# Main.net
KiCad netlist of a schematic drawn in Altium Designer
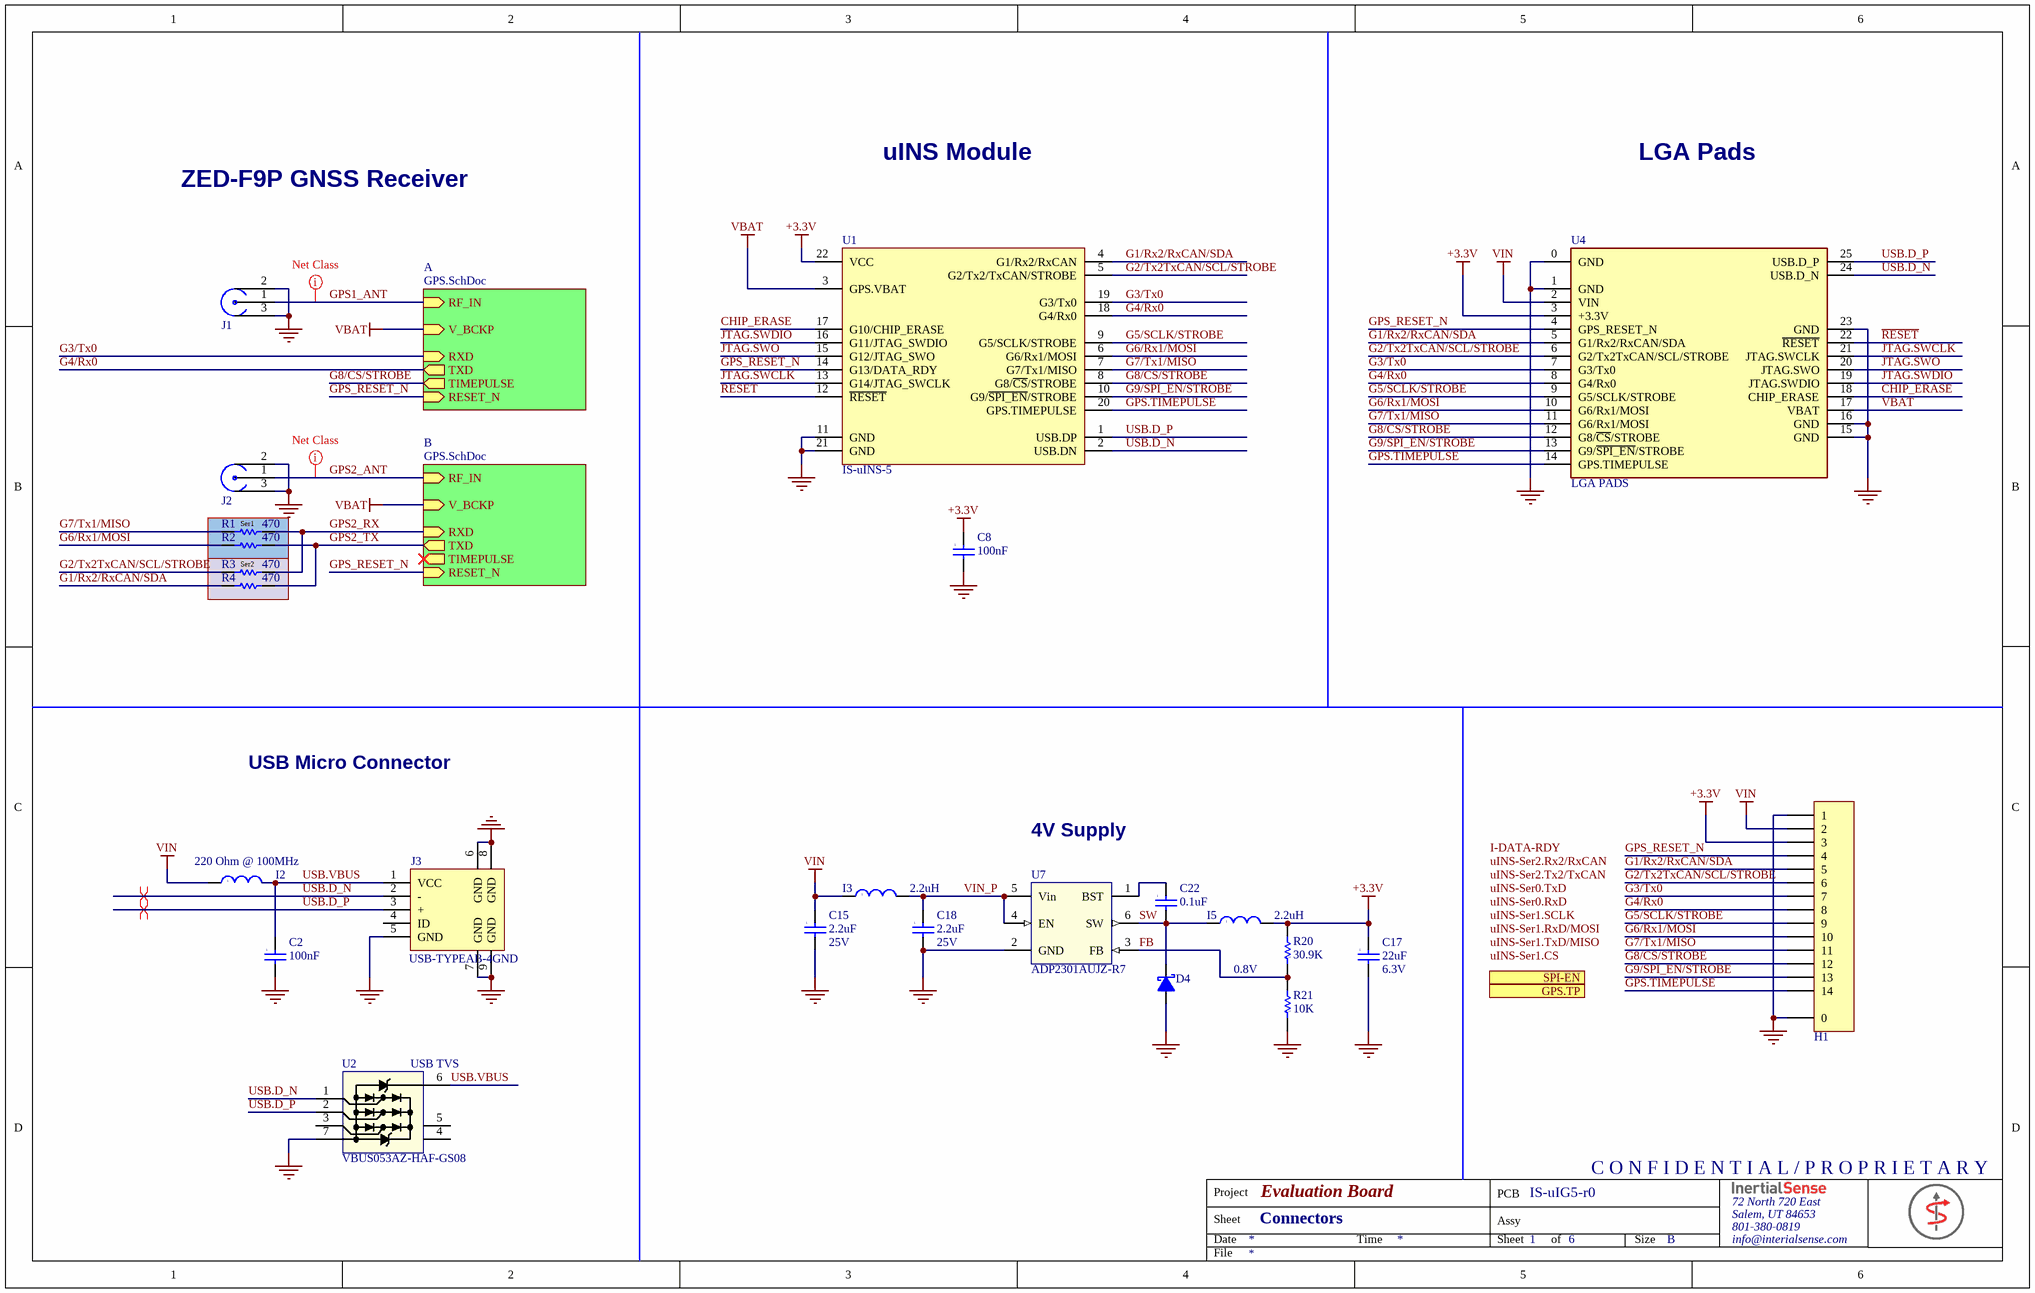
[diagram p0: Main.SchDoc]

(export (version "E")
  (design (tool "Eeschema 10.0.6"))
  (components
    (comp (ref "C2")
      (value "100nF")
      (footprint "0402")
      (description "CAP CER .10UF 50V X7R 10% 0402")
      (fields
        (field (name "MANUFACTURER") "TDK Corporation")
        (field (name "MANUFACTURER PART NUMBER") "C1005X7R1H104K")
        (field (name "PUBLISHER") "Altium Limited")
      )
      (libsource (lib "General") (part "Cap"))
    )
    (comp (ref "C8")
      (value "100nF")
      (footprint "0402")
      (description "CAP CER .10UF 50V X7R 10% 0402")
      (fields
        (field (name "MANUFACTURER") "TDK Corporation")
        (field (name "MANUFACTURER PART NUMBER") "C1005X7R1H104K")
        (field (name "PUBLISHER") "Altium Limited")
      )
      (libsource (lib "General") (part "Cap"))
    )
    (comp (ref "C15")
      (value "2.2uF")
      (footprint "0603")
      (description "CAP CER 2.2UF 25V X6S 0603")
      (fields
        (field (name "MANUFACTURER") "Murata")
        (field (name "MANUFACTURER PART NUMBER") "GRT188C81E225KE13D")
        (field (name "VOLTAGE RATING") "25V")
        (field (name "PUBLISHER") "Altium Limited")
      )
      (libsource (lib "") (part "Cap_1"))
    )
    (comp (ref "C17")
      (value "22uF")
      (footprint "0603")
      (description "CAP CER 22UF 6.3V X6S 0603")
      (fields
        (field (name "MANUFACTURER") "Murata")
        (field (name "MANUFACTURER PART NUMBER") "GRM188C80J226ME15D")
        (field (name "VOLTAGE RATING") "6.3V")
        (field (name "PUBLISHER") "Altium Limited")
      )
      (libsource (lib "") (part "Cap_1"))
    )
    (comp (ref "C18")
      (value "2.2uF")
      (footprint "0603")
      (description "CAP CER 2.2UF 25V X6S 0603")
      (fields
        (field (name "MANUFACTURER") "Murata")
        (field (name "MANUFACTURER PART NUMBER") "GRT188C81E225KE13D")
        (field (name "VOLTAGE RATING") "25V")
        (field (name "PUBLISHER") "Altium Limited")
      )
      (libsource (lib "") (part "Cap_1"))
    )
    (comp (ref "C22")
      (value "0.1uF")
      (footprint "0402")
      (description "CAP CER 0.1UF 50V X7R 0402")
      (fields
        (field (name "MANUFACTURER") "TDK")
        (field (name "MANUFACTURER PART NUMBER") "CGA2B3X7R1H104K050BB")
        (field (name "PUBLISHER") "Altium Limited")
      )
      (libsource (lib "") (part "Cap_1"))
    )
    (comp (ref "D4")
      (value "Diode - Schottky")
      (footprint "D0603B")
      (description "DIODE SCHOTTKY 30V 2A 0603")
      (fields
        (field (name "MANUFACTURER") "Vishay")
        (field (name "MANUFACTURER PART NUMBER") "VSKY20301608-G4-08")
      )
      (libsource (lib "General") (part "Diode - Schottky"))
    )
    (comp (ref "H1")
      (value "Hdr - 14pin - mount")
      (footprint "SM14B-GHS-TB(LF)(SN)")
      (description "Conn Shrouded Header HDR 14 POS 1.25mm Solder ST Top Entry SMD T/R")
      (fields
        (field (name "MANUFACTURER") "JST")
        (field (name "MANUFACTURER PART NUMBER") "SM14B-GHS-TB(LF)(SN)")
      )
      (libsource (lib "Connectors") (part "Hdr - 14pin - mount"))
    )
    (comp (ref "I2")
      (value "220 Ohm @ 100MHz")
      (footprint "I0603")
      (description "FERRITE CHIP 220 OHM 2500MA 0603")
      (fields
        (field (name "MANUFACTURER") "Murata Electronics North America")
        (field (name "MANUFACTURER PART NUMBER") "BLM18SG221TN1D")
      )
      (libsource (lib "") (part "Inductor_1"))
    )
    (comp (ref "I3")
      (value "2.2uH")
      (footprint "0806")
      (description "FIXED IND 2.2UH 1.2A 110 MOHM")
      (fields
        (field (name "MANUFACTURER") "TDK")
        (field (name "MANUFACTURER PART NUMBER") "MLP2016H2R2MT0S1")
      )
      (libsource (lib "General") (part "Inductor"))
    )
    (comp (ref "I5")
      (value "2.2uH")
      (footprint "0806")
      (description "FIXED IND 2.2UH 1.2A 110 MOHM")
      (fields
        (field (name "MANUFACTURER") "TDK")
        (field (name "MANUFACTURER PART NUMBER") "MLP2016H2R2MT0S1")
      )
      (libsource (lib "General") (part "Inductor"))
    )
    (comp (ref "J1")
      (value "RF - GND x 2")
      (footprint "RF UMC SMD")
      (description "CONN UMC RCPT STR 50 OHM SMD")
      (fields
        (field (name "MANUFACTURER") "Emerson Network Power Connectivity Johnson")
        (field (name "MANUFACTURER PART NUMBER") "128-0711-201")
      )
      (libsource (lib "Connectors") (part "RF - GND x 2"))
    )
    (comp (ref "J2")
      (value "RF - GND x 2")
      (footprint "RF UMC SMD")
      (description "CONN UMC RCPT STR 50 OHM SMD")
      (fields
        (field (name "MANUFACTURER") "Emerson Network Power Connectivity Johnson")
        (field (name "MANUFACTURER PART NUMBER") "128-0711-201")
      )
      (libsource (lib "Connectors") (part "RF - GND x 2"))
    )
    (comp (ref "J3")
      (value "USB-TYPEAB-4GND")
      (footprint "USB Micro AB R/A THR")
      (description "CONN USB AB 4POS")
      (fields
        (field (name "MANUFACTURER") "Amphenol FCI")
        (field (name "MANUFACTURER PART NUMBER") "10118194-0001LF")
      )
      (libsource (lib "Connectors") (part "USB-TYPEAB-4GND"))
    )
    (comp (ref "R1")
      (value "470")
      (footprint "R0402")
      (description "RES 470 OHM 1/16W 1% 0402 SMD")
      (fields
        (field (name "MANUFACTURER") "Vishay Dale")
        (field (name "MANUFACTURER PART NUMBER") "CRCW0402470RFKED")
      )
      (libsource (lib "") (part "Res_1"))
    )
    (comp (ref "R2")
      (value "470")
      (footprint "R0402")
      (description "RES 470 OHM 1/16W 1% 0402 SMD")
      (fields
        (field (name "MANUFACTURER") "Vishay Dale")
        (field (name "MANUFACTURER PART NUMBER") "CRCW0402470RFKED")
      )
      (libsource (lib "") (part "Res_1"))
    )
    (comp (ref "R3")
      (value "470")
      (footprint "R0402")
      (description "RES 470 OHM 1/16W 1% 0402 SMD")
      (fields
        (field (name "MANUFACTURER") "Vishay Dale")
        (field (name "MANUFACTURER PART NUMBER") "CRCW0402470RFKED")
      )
      (libsource (lib "") (part "Res_1"))
    )
    (comp (ref "R4")
      (value "470")
      (footprint "R0402")
      (description "RES 470 OHM 1/16W 1% 0402 SMD")
      (fields
        (field (name "MANUFACTURER") "Vishay Dale")
        (field (name "MANUFACTURER PART NUMBER") "CRCW0402470RFKED")
      )
      (libsource (lib "") (part "Res_1"))
    )
    (comp (ref "R20")
      (value "30.9K")
      (footprint "R0402")
      (description "RES TF 30.9K OHM 1% 1/16W 0402")
      (fields
        (field (name "MANUFACTURER") "Stackpole Electronics Inc")
        (field (name "MANUFACTURER PART NUMBER") "RMCF0402FT30K9")
      )
      (libsource (lib "General") (part "Res"))
    )
    (comp (ref "R21")
      (value "10K")
      (footprint "R0402")
      (description "RES 10.0K OHM 1/16W 1% 0402 SMD")
      (fields
        (field (name "MANUFACTURER") "Yageo")
        (field (name "MANUFACTURER PART NUMBER") "RC0402FR-0710KL")
      )
      (libsource (lib "General") (part "Res"))
    )
    (comp (ref "U1")
      (value "uINS")
      (footprint "IS-uINS-5.0")
      (description "Inertial Sense uINS")
      (fields
        (field (name "MANUFACTURER") "Inertial Sense")
        (field (name "MANUFACTURER PART NUMBER") "IS-uINS-5")
      )
      (libsource (lib "IS-uINS-5") (part "IS-uINS-5.0"))
    )
    (comp (ref "U2")
      (value "VBUS053")
      (footprint "QFN50P160X160X60-6N")
      (description "ESD SUPPRESS 5.5V 36W 3-Line USB")
      (fields
        (field (name "MANUFACTURER") "Vishay Semiconductors")
        (field (name "MANUFACTURER PART NUMBER") "VBUS053AZ-HAF-GS08")
      )
      (libsource (lib "ICs") (part "VBUS053"))
    )
    (comp (ref "U4")
      (value "LGA PADS")
      (footprint "uIG5p1_LGA")
      (description "Inertial Sense uIG5 GNSS INS Module")
      (libsource (lib "Sensors") (part "uIG5p0_LGA"))
    )
    (comp (ref "U7")
      (value "ADP2301")
      (footprint "MO-178-AB")
      (description "IC BUCK ADJ 1.2A 6TSOT")
      (fields
        (field (name "MANUFACTURER") "Analog Devices Inc")
        (field (name "MANUFACTURER PART NUMBER") "ADP2301AUJZ-R7")
      )
      (libsource (lib "ICs") (part "ADP2301"))
    )
  )
  (nets
    (net (code "1") (name "+3.3V") (class "Default")
      (node (ref "C17") (pin "1") (pinfunction "1_1") (pintype "passive"))
      (node (ref "C8") (pin "1") (pinfunction "1_1") (pintype "passive"))
      (node (ref "H1") (pin "3") (pinfunction "3_3") (pintype "passive"))
      (node (ref "I5") (pin "2") (pinfunction "2_2") (pintype "passive"))
      (node (ref "R20") (pin "2") (pinfunction "2_2") (pintype "passive"))
      (node (ref "U1") (pin "22") (pinfunction "VCC_22") (pintype "power_in"))
      (node (ref "U4") (pin "3") (pinfunction "+3.3V_3") (pintype "passive"))
    )
    (net (code "2") (name "/CHIP_ERASE") (class "Default")
      (node (ref "U1") (pin "17") (pinfunction "G10/CHIP_ERASE_17") (pintype "passive"))
      (node (ref "U4") (pin "18") (pinfunction "CHIP_ERASE_18") (pintype "passive"))
    )
    (net (code "3") (name "/FB") (class "Default")
      (node (ref "R20") (pin "1") (pinfunction "1_1") (pintype "passive"))
      (node (ref "R21") (pin "2") (pinfunction "2_2") (pintype "passive"))
      (node (ref "U7") (pin "3") (pinfunction "FB_3") (pintype "input"))
    )
    (net (code "4") (name "/G1{slash}Rx2{slash}RxCAN{slash}SDA") (class "Default")
      (node (ref "H1") (pin "5") (pinfunction "5_5") (pintype "passive"))
      (node (ref "R4") (pin "1") (pinfunction "1_1") (pintype "passive"))
      (node (ref "U1") (pin "4") (pinfunction "G1/Rx2/RxCAN_4") (pintype "passive"))
      (node (ref "U4") (pin "5") (pinfunction "G1/Rx2/RxCAN/SDA_5") (pintype "passive"))
    )
    (net (code "5") (name "/G2{slash}Tx2TxCAN{slash}SCL{slash}STROBE") (class "Default")
      (node (ref "H1") (pin "6") (pinfunction "6_6") (pintype "passive"))
      (node (ref "R3") (pin "1") (pinfunction "1_1") (pintype "passive"))
      (node (ref "U1") (pin "5") (pinfunction "G2/Tx2/TxCAN/STROBE_5") (pintype "passive"))
      (node (ref "U4") (pin "6") (pinfunction "G2/Tx2TxCAN/SCL/STROBE_6") (pintype "passive"))
    )
    (net (code "6") (name "/G3{slash}Tx0") (class "Default")
      (node (ref "H1") (pin "7") (pinfunction "7_7") (pintype "passive"))
      (node (ref "U1") (pin "19") (pinfunction "G3/Tx0_19") (pintype "passive"))
      (node (ref "U4") (pin "7") (pinfunction "G3/Tx0_7") (pintype "passive"))
    )
    (net (code "7") (name "/G4{slash}Rx0") (class "Default")
      (node (ref "H1") (pin "8") (pinfunction "8_8") (pintype "passive"))
      (node (ref "U1") (pin "18") (pinfunction "G4/Rx0_18") (pintype "passive"))
      (node (ref "U4") (pin "8") (pinfunction "G4/Rx0_8") (pintype "passive"))
    )
    (net (code "8") (name "/G5{slash}SCLK{slash}STROBE") (class "Default")
      (node (ref "H1") (pin "9") (pinfunction "9_9") (pintype "passive"))
      (node (ref "U1") (pin "9") (pinfunction "G5/SCLK/STROBE_9") (pintype "passive"))
      (node (ref "U4") (pin "9") (pinfunction "G5/SCLK/STROBE_9") (pintype "passive"))
    )
    (net (code "9") (name "/G6{slash}Rx1{slash}MOSI") (class "Default")
      (node (ref "H1") (pin "10") (pinfunction "10_10") (pintype "passive"))
      (node (ref "R2") (pin "1") (pinfunction "1_1") (pintype "passive"))
      (node (ref "U1") (pin "6") (pinfunction "G6/Rx1/MOSI_6") (pintype "passive"))
      (node (ref "U4") (pin "10") (pinfunction "G6/Rx1/MOSI_10") (pintype "passive"))
    )
    (net (code "10") (name "/G7{slash}Tx1{slash}MISO") (class "Default")
      (node (ref "H1") (pin "11") (pinfunction "11_11") (pintype "passive"))
      (node (ref "R1") (pin "1") (pinfunction "1_1") (pintype "passive"))
      (node (ref "U1") (pin "7") (pinfunction "G7/Tx1/MISO_7") (pintype "passive"))
      (node (ref "U4") (pin "11") (pinfunction "G6/Rx1/MOSI_11") (pintype "passive"))
    )
    (net (code "11") (name "/G8{slash}~{CS}{slash}STROBE") (class "Default")
      (node (ref "H1") (pin "12") (pinfunction "12_12") (pintype "passive"))
      (node (ref "U1") (pin "8") (pinfunction "G8/~{CS}/STROBE_8") (pintype "passive"))
      (node (ref "U4") (pin "12") (pinfunction "G8/~{CS}/STROBE_12") (pintype "passive"))
    )
    (net (code "12") (name "/G9{slash}~{SPI_EN}{slash}STROBE") (class "Default")
      (node (ref "H1") (pin "13") (pinfunction "13_13") (pintype "passive"))
      (node (ref "U1") (pin "10") (pinfunction "G9/~{SPI_EN}/STROBE_10") (pintype "passive"))
      (node (ref "U4") (pin "13") (pinfunction "G9/~{SPI_EN}/STROBE_13") (pintype "passive"))
    )
    (net (code "13") (name "/GPS.TIMEPULSE") (class "Default")
      (node (ref "H1") (pin "14") (pinfunction "14_14") (pintype "passive"))
      (node (ref "U1") (pin "20") (pinfunction "GPS.TIMEPULSE_20") (pintype "passive"))
      (node (ref "U4") (pin "14") (pinfunction "GPS.TIMEPULSE_14") (pintype "passive"))
    )
    (net (code "15") (name "/GPS1_ANT") (class "Default")
      (node (ref "J1") (pin "1") (pinfunction "1_1") (pintype "passive"))
    )
    (net (code "16") (name "/GPS2_ANT") (class "Default")
      (node (ref "J2") (pin "1") (pinfunction "1_1") (pintype "passive"))
    )
    (net (code "17") (name "/GPS2_RX") (class "Default")
      (node (ref "R1") (pin "2") (pinfunction "2_2") (pintype "passive"))
      (node (ref "R3") (pin "2") (pinfunction "2_2") (pintype "passive"))
    )
    (net (code "18") (name "/GPS2_TX") (class "Default")
      (node (ref "R2") (pin "2") (pinfunction "2_2") (pintype "passive"))
      (node (ref "R4") (pin "2") (pinfunction "2_2") (pintype "passive"))
    )
    (net (code "19") (name "/GPS_RESET_N") (class "Default")
      (node (ref "H1") (pin "4") (pinfunction "4_4") (pintype "passive"))
      (node (ref "U1") (pin "14") (pinfunction "G13/DATA_RDY_14") (pintype "passive"))
      (node (ref "U4") (pin "4") (pinfunction "GPS_RESET_N_4") (pintype "passive"))
    )
    (net (code "21") (name "/JTAG.SWCLK") (class "Default")
      (node (ref "U1") (pin "13") (pinfunction "G14/JTAG_SWCLK_13") (pintype "passive"))
      (node (ref "U4") (pin "21") (pinfunction "JTAG.SWCLK_21") (pintype "passive"))
    )
    (net (code "22") (name "/JTAG.SWDIO") (class "Default")
      (node (ref "U1") (pin "16") (pinfunction "G11/JTAG_SWDIO_16") (pintype "passive"))
      (node (ref "U4") (pin "19") (pinfunction "JTAG.SWDIO_19") (pintype "passive"))
    )
    (net (code "23") (name "/JTAG.SWO") (class "Default")
      (node (ref "U1") (pin "15") (pinfunction "G12/JTAG_SWO_15") (pintype "passive"))
      (node (ref "U4") (pin "20") (pinfunction "JTAG.SWO_20") (pintype "passive"))
    )
    (net (code "24") (name "/RESET") (class "Default")
      (node (ref "U1") (pin "12") (pinfunction "~{RESET}_12") (pintype "passive"))
      (node (ref "U4") (pin "22") (pinfunction "~{RESET}_22") (pintype "passive"))
    )
    (net (code "26") (name "/SW") (class "Default")
      (node (ref "C22") (pin "2") (pinfunction "2_2") (pintype "passive"))
      (node (ref "D4") (pin "C") (pinfunction "C_C") (pintype "passive"))
      (node (ref "I5") (pin "1") (pinfunction "1_1") (pintype "passive"))
      (node (ref "U7") (pin "6") (pinfunction "SW_6") (pintype "output"))
    )
    (net (code "28") (name "/USB.D_N") (class "Default")
      (node (ref "J3") (pin "2") (pinfunction "-_2") (pintype "passive"))
      (node (ref "U1") (pin "2") (pinfunction "USB.DN_2") (pintype "passive"))
      (node (ref "U2") (pin "1") (pintype "passive"))
      (node (ref "U4") (pin "24") (pinfunction "USB.D_N_24") (pintype "passive"))
    )
    (net (code "29") (name "/USB.D_P") (class "Default")
      (node (ref "J3") (pin "3") (pinfunction "+_3") (pintype "passive"))
      (node (ref "U1") (pin "1") (pinfunction "USB.DP_1") (pintype "passive"))
      (node (ref "U2") (pin "2") (pintype "passive"))
      (node (ref "U4") (pin "25") (pinfunction "USB.D_P_25") (pintype "passive"))
    )
    (net (code "30") (name "/USB.VBUS") (class "Default")
      (node (ref "C2") (pin "1") (pinfunction "1_1") (pintype "passive"))
      (node (ref "I2") (pin "2") (pinfunction "2_2") (pintype "passive"))
      (node (ref "J3") (pin "1") (pinfunction "VCC_1") (pintype "passive"))
      (node (ref "U2") (pin "6") (pintype "passive"))
    )
    (net (code "31") (name "/VIN_P") (class "Default")
      (node (ref "C18") (pin "1") (pinfunction "1_1") (pintype "passive"))
      (node (ref "I3") (pin "2") (pinfunction "2_2") (pintype "passive"))
      (node (ref "U7") (pin "4") (pinfunction "EN_4") (pintype "input"))
      (node (ref "U7") (pin "5") (pinfunction "Vin_5") (pintype "power_in"))
    )
    (net (code "40") (name "GND") (class "Default")
      (node (ref "C15") (pin "2") (pinfunction "2_2") (pintype "passive"))
      (node (ref "C17") (pin "2") (pinfunction "2_2") (pintype "passive"))
      (node (ref "C18") (pin "2") (pinfunction "2_2") (pintype "passive"))
      (node (ref "C2") (pin "2") (pinfunction "2_2") (pintype "passive"))
      (node (ref "C8") (pin "2") (pinfunction "2_2") (pintype "passive"))
      (node (ref "D4") (pin "A") (pinfunction "A_A") (pintype "passive"))
      (node (ref "H1") (pin "0") (pinfunction "0_0") (pintype "passive"))
      (node (ref "H1") (pin "1") (pinfunction "1_1") (pintype "passive"))
      (node (ref "J1") (pin "2") (pinfunction "2_2") (pintype "passive"))
      (node (ref "J1") (pin "3") (pinfunction "3_3") (pintype "passive"))
      (node (ref "J2") (pin "2") (pinfunction "2_2") (pintype "passive"))
      (node (ref "J2") (pin "3") (pinfunction "3_3") (pintype "passive"))
      (node (ref "J3") (pin "5") (pinfunction "GND_5") (pintype "passive"))
      (node (ref "J3") (pin "6") (pinfunction "GND_6") (pintype "passive"))
      (node (ref "J3") (pin "7") (pinfunction "GND_7") (pintype "passive"))
      (node (ref "J3") (pin "8") (pinfunction "GND_8") (pintype "passive"))
      (node (ref "J3") (pin "9") (pinfunction "GND_9") (pintype "passive"))
      (node (ref "R21") (pin "1") (pinfunction "1_1") (pintype "passive"))
      (node (ref "U1") (pin "11") (pinfunction "GND_11") (pintype "power_in"))
      (node (ref "U1") (pin "21") (pinfunction "GND_21") (pintype "power_in"))
      (node (ref "U2") (pin "7") (pintype "passive"))
      (node (ref "U4") (pin "0") (pinfunction "GND_0") (pintype "passive"))
      (node (ref "U4") (pin "1") (pinfunction "GND_1") (pintype "passive"))
      (node (ref "U4") (pin "15") (pinfunction "GND_15") (pintype "passive"))
      (node (ref "U4") (pin "16") (pinfunction "GND_16") (pintype "passive"))
      (node (ref "U4") (pin "23") (pinfunction "GND_23") (pintype "passive"))
      (node (ref "U7") (pin "2") (pinfunction "GND_2") (pintype "power_in"))
    )
    (net (code "41") (name "Net-(U7-BST)") (class "Default")
      (node (ref "C22") (pin "1") (pinfunction "1_1") (pintype "passive"))
      (node (ref "U7") (pin "1") (pinfunction "BST_1") (pintype "passive"))
    )
    (net (code "42") (name "VBAT") (class "Default")
      (node (ref "U1") (pin "3") (pinfunction "GPS.VBAT_3") (pintype "passive"))
      (node (ref "U4") (pin "17") (pinfunction "VBAT_17") (pintype "passive"))
    )
    (net (code "43") (name "VIN") (class "Default")
      (node (ref "C15") (pin "1") (pinfunction "1_1") (pintype "passive"))
      (node (ref "H1") (pin "2") (pinfunction "2_2") (pintype "passive"))
      (node (ref "I2") (pin "1") (pinfunction "1_1") (pintype "passive"))
      (node (ref "I3") (pin "1") (pinfunction "1_1") (pintype "passive"))
      (node (ref "U4") (pin "2") (pinfunction "VIN_2") (pintype "passive"))
    )
    (net (code "44") (name "unconnected-(J3-ID-Pad4)") (class "Default")
      (node (ref "J3") (pin "4") (pinfunction "ID_4") (pintype "passive"))
    )
    (net (code "45") (name "unconnected-(U2-Pad3)") (class "Default")
      (node (ref "U2") (pin "3") (pintype "passive"))
    )
    (net (code "46") (name "unconnected-(U2-nc-Pad4)") (class "Default")
      (node (ref "U2") (pin "4") (pinfunction "nc_4") (pintype "passive"))
    )
    (net (code "47") (name "unconnected-(U2-nc-Pad5)") (class "Default")
      (node (ref "U2") (pin "5") (pinfunction "nc_5") (pintype "passive"))
    )
  )
)
